# DB_Power-X01.net
KiCad netlist of a schematic drawn in Altium Designer
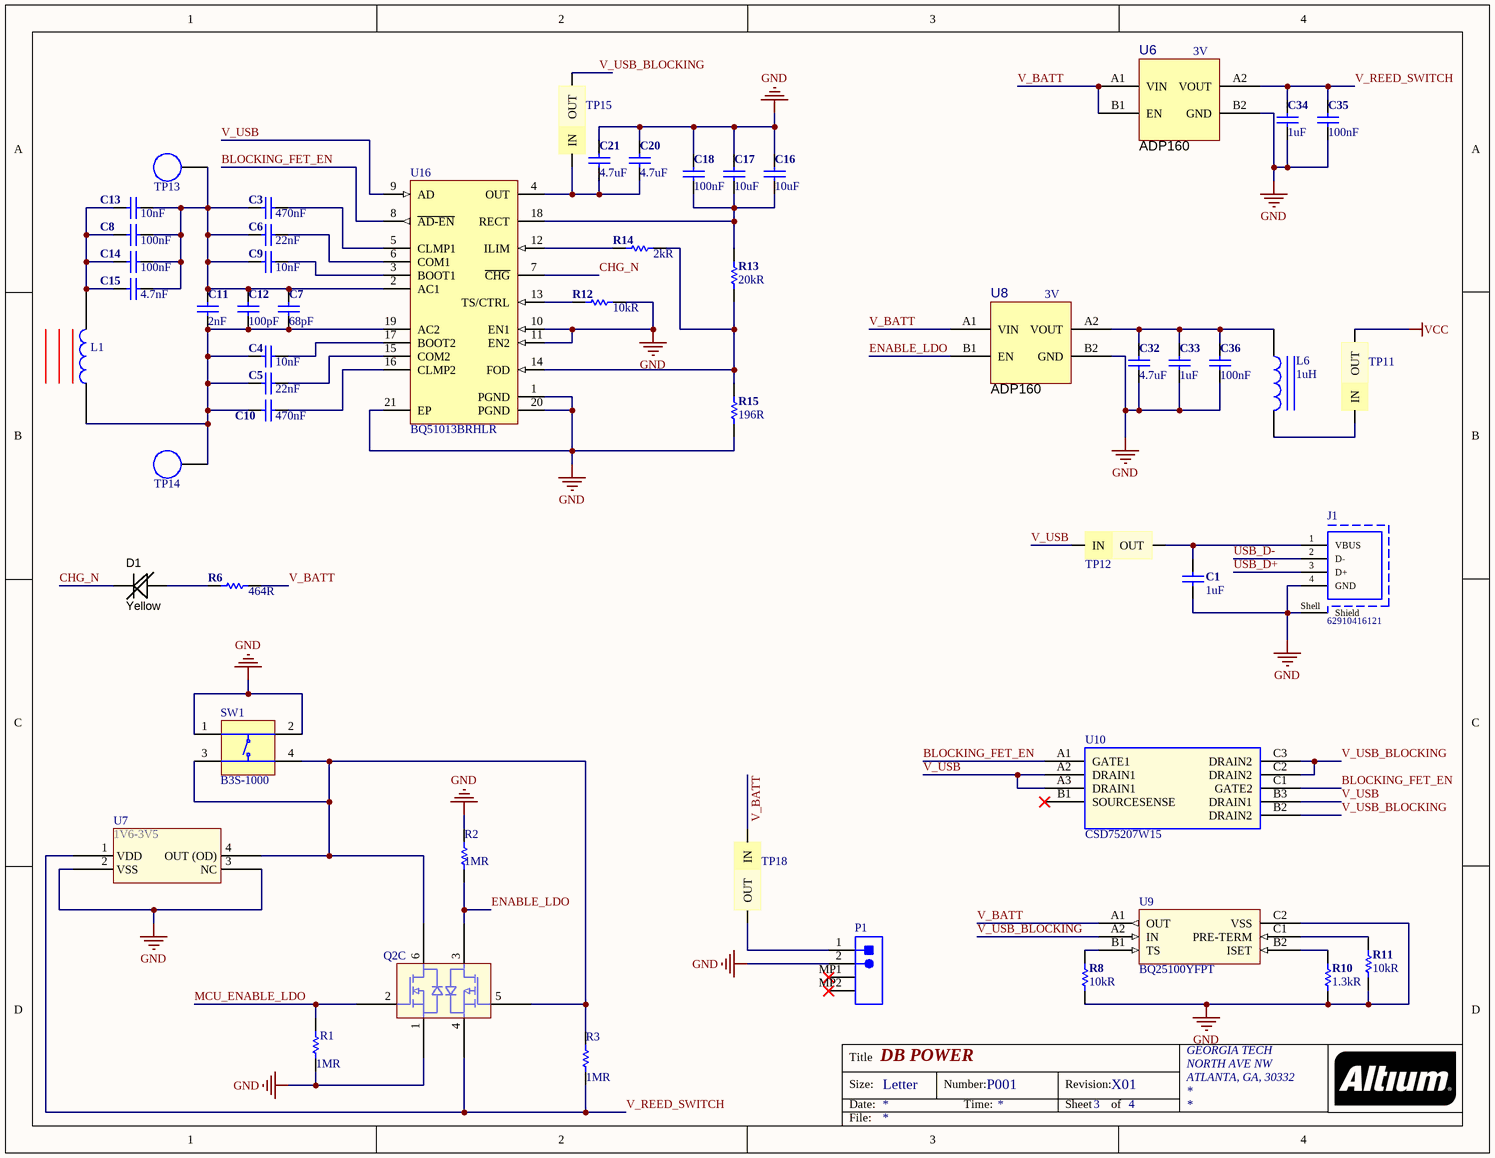
[diagram p0: DB_Power-X01.SchDoc]

(export (version "E")
  (design (tool "Eeschema 10.0.6"))
  (components
    (comp (ref "C1")
      (value "1uF")
      (footprint "C0402")
      (fields
        (field (name "MANUFACTURER") "Yageo")
        (field (name "MANUFACTURER PART NUMBER") "CC0402MRX5R5BB105")
        (field (name "TOLERANCE") "20%")
      )
      (libsource (lib "DB-X01") (part "C-0402(1005)"))
    )
    (comp (ref "C3")
      (value "470nF")
      (footprint "C0402")
      (fields
        (field (name "MANUFACTURER") "Murata")
        (field (name "MANUFACTURER PART NUMBER") "GRT155R61E474ME01D")
        (field (name "TOLERANCE") "20%")
      )
      (libsource (lib "DB-X01") (part "C-0402(1005)"))
    )
    (comp (ref "C4")
      (value "10nF")
      (footprint "C0402")
      (fields
        (field (name "MANUFACTURER") "KEMET")
        (field (name "MANUFACTURER PART NUMBER") "C0402C103J3RACTU")
        (field (name "TOLERANCE") "5%")
      )
      (libsource (lib "DB-X01") (part "C-0402(1005)"))
    )
    (comp (ref "C5")
      (value "22nF")
      (footprint "C0402")
      (fields
        (field (name "MANUFACTURER") "Murata")
        (field (name "MANUFACTURER PART NUMBER") "GRM155R71E223KA61D")
        (field (name "TOLERANCE") "10%")
      )
      (libsource (lib "DB-X01") (part "C-0402(1005)"))
    )
    (comp (ref "C6")
      (value "22nF")
      (footprint "C0402")
      (fields
        (field (name "MANUFACTURER") "Murata")
        (field (name "MANUFACTURER PART NUMBER") "GRM155R71E223KA61D")
        (field (name "TOLERANCE") "10%")
      )
      (libsource (lib "DB-X01") (part "C-0402(1005)"))
    )
    (comp (ref "C7")
      (value "68pF")
      (footprint "C0402")
      (fields
        (field (name "MANUFACTURER") "KEMET")
        (field (name "MANUFACTURER PART NUMBER") "CBR04C680F3GAC")
        (field (name "TOLERANCE") "1%")
      )
      (libsource (lib "DB-X01") (part "C-0402(1005)"))
    )
    (comp (ref "C8")
      (value "100nF")
      (footprint "C0402")
      (fields
        (field (name "MANUFACTURER") "Taiyo Yuden")
        (field (name "MANUFACTURER PART NUMBER") "TMK105BJ104KV-F")
        (field (name "TOLERANCE") "10%")
      )
      (libsource (lib "DB-X01") (part "C-0402(1005)"))
    )
    (comp (ref "C9")
      (value "10nF")
      (footprint "C0402")
      (fields
        (field (name "MANUFACTURER") "KEMET")
        (field (name "MANUFACTURER PART NUMBER") "C0402C103J3RACTU")
        (field (name "TOLERANCE") "5%")
      )
      (libsource (lib "DB-X01") (part "C-0402(1005)"))
    )
    (comp (ref "C10")
      (value "470nF")
      (footprint "C0402")
      (fields
        (field (name "MANUFACTURER") "Murata")
        (field (name "MANUFACTURER PART NUMBER") "GRT155R61E474ME01D")
        (field (name "TOLERANCE") "20%")
      )
      (libsource (lib "DB-X01") (part "C-0402(1005)"))
    )
    (comp (ref "C11")
      (value "2nF")
      (footprint "C0402")
      (fields
        (field (name "MANUFACTURER") "KEMET")
        (field (name "MANUFACTURER PART NUMBER") "C0402C202J3GACTU")
        (field (name "TOLERANCE") "5%")
      )
      (libsource (lib "DB-X01") (part "C-0402(1005)"))
    )
    (comp (ref "C12")
      (value "100pF")
      (footprint "C0402")
      (fields
        (field (name "MANUFACTURER") "KEMET")
        (field (name "MANUFACTURER PART NUMBER") "CBR04C101F3GAC")
        (field (name "TOLERANCE") "1%")
      )
      (libsource (lib "DB-X01") (part "C-0402(1005)"))
    )
    (comp (ref "C13")
      (value "10nF")
      (footprint "C0402")
      (fields
        (field (name "MANUFACTURER") "Yageo")
        (field (name "MANUFACTURER PART NUMBER") "CC0402JRX7R8BB103")
        (field (name "TOLERANCE") "5%")
      )
      (libsource (lib "DB-X01") (part "C-0402(1005)"))
    )
    (comp (ref "C14")
      (value "100nF")
      (footprint "C0402")
      (fields
        (field (name "MANUFACTURER") "Taiyo Yuden")
        (field (name "MANUFACTURER PART NUMBER") "TMK105BJ104KV-F")
        (field (name "TOLERANCE") "10%")
      )
      (libsource (lib "DB-X01") (part "C-0402(1005)"))
    )
    (comp (ref "C15")
      (value "4.7nF")
      (footprint "C0402")
      (fields
        (field (name "MANUFACTURER") "Yageo")
        (field (name "MANUFACTURER PART NUMBER") "CC0402JRX7R8BB472")
        (field (name "TOLERANCE") "5%")
      )
      (libsource (lib "DB-X01") (part "C-0402(1005)"))
    )
    (comp (ref "C16")
      (value "10uF")
      (footprint "C0603")
      (fields
        (field (name "MANUFACTURER") "Murata")
        (field (name "MANUFACTURER PART NUMBER") "GRM188R61E106MA73J")
        (field (name "TOLERANCE") "20%")
      )
      (libsource (lib "DB-X01") (part "C-0603(1608)"))
    )
    (comp (ref "C17")
      (value "10uF")
      (footprint "C0603")
      (fields
        (field (name "MANUFACTURER") "Murata")
        (field (name "MANUFACTURER PART NUMBER") "GRM188R61E106MA73J")
        (field (name "TOLERANCE") "20%")
      )
      (libsource (lib "DB-X01") (part "C-0603(1608)"))
    )
    (comp (ref "C18")
      (value "100nF")
      (footprint "C0603")
      (fields
        (field (name "MANUFACTURER") "Yageo")
        (field (name "MANUFACTURER PART NUMBER") "CC0402ZRY5V8BB104")
        (field (name "TOLERANCE") "80%")
      )
      (libsource (lib "DB-X01") (part "C-0603(1608)"))
    )
    (comp (ref "C20")
      (value "4.7uF")
      (footprint "C0402")
      (description "0402 10 V 4.7 uF ±20% Tolerance X5R Multilayer Ceramic Chip Capacitor")
      (fields
        (field (name "MANUFACTURER") "Murata")
        (field (name "MANUFACTURER PART NUMBER") "GRM155R61A475MEAAD")
      )
      (libsource (lib "DB-X01") (part "C-0402(1005)"))
    )
    (comp (ref "C21")
      (value "4.7uF")
      (footprint "C0402")
      (description "0402 10 V 4.7 uF ±20% Tolerance X5R Multilayer Ceramic Chip Capacitor")
      (fields
        (field (name "MANUFACTURER") "Murata")
        (field (name "MANUFACTURER PART NUMBER") "GRM155R61A475MEAAD")
      )
      (libsource (lib "DB-X01") (part "C-0402(1005)"))
    )
    (comp (ref "C32")
      (value "4.7uF")
      (footprint "C0402")
      (description "0402 10 V 4.7 uF ±20% Tolerance X5R Multilayer Ceramic Chip Capacitor")
      (fields
        (field (name "MANUFACTURER") "Murata")
        (field (name "MANUFACTURER PART NUMBER") "GRM155R61A475MEAAD")
      )
      (libsource (lib "DB-X01") (part "C-0402(1005)"))
    )
    (comp (ref "C33")
      (value "1uF")
      (footprint "C0402")
      (fields
        (field (name "MANUFACTURER") "Yageo")
        (field (name "MANUFACTURER PART NUMBER") "CC0402MRX5R5BB105")
        (field (name "TOLERANCE") "20%")
      )
      (libsource (lib "DB-X01") (part "C-0402(1005)"))
    )
    (comp (ref "C34")
      (value "1uF")
      (footprint "C0402")
      (fields
        (field (name "MANUFACTURER") "Yageo")
        (field (name "MANUFACTURER PART NUMBER") "CC0402MRX5R5BB105")
        (field (name "TOLERANCE") "20%")
      )
      (libsource (lib "DB-X01") (part "C-0402(1005)"))
    )
    (comp (ref "C35")
      (value "100nF")
      (footprint "C0402")
      (fields
        (field (name "MANUFACTURER") "Taiyo Yuden")
        (field (name "MANUFACTURER PART NUMBER") "TMK105BJ104KV-F")
        (field (name "TOLERANCE") "10%")
      )
      (libsource (lib "DB-X01") (part "C-0402(1005)"))
    )
    (comp (ref "C36")
      (value "100nF")
      (footprint "C0402")
      (fields
        (field (name "MANUFACTURER") "Taiyo Yuden")
        (field (name "MANUFACTURER PART NUMBER") "TMK105BJ104KV-F")
        (field (name "TOLERANCE") "10%")
      )
      (libsource (lib "DB-X01") (part "C-0402(1005)"))
    )
    (comp (ref "D1")
      (value "Yellow")
      (footprint "LED_0402")
      (description "Single Color LED, Super Bright Yellow, Water Clear, 0.8mm")
      (fields
        (field (name "MANUFACTURER") "Kingbright")
        (field (name "MANUFACTURER PART NUMBER") "APHHS1005SYCK")
      )
      (libsource (lib "DB-X01") (part "LED_0402(1005)"))
    )
    (comp (ref "J1")
      (value "62910416121")
      (footprint "62910416121")
      (description "USB 2.0 Type B Receptacle WR-COM, Horizontal, SMT, with Pads and Pegs")
      (fields (field (name "MANUFACTURER") "Wurth Electronics"))
      (libsource (lib "Altium Content Vault") (part "WE-USB-4-1SHLD"))
    )
    (comp (ref "L1")
      (value "WIRELESS CHARGING COIL, RECEIVER")
      (footprint "760308101219")
      (description "General Purpose Inductor, 11.8uH, 10%, 1 Element")
      (fields
        (field (name "MANUFACTURER") "Wurth Electronics")
        (field (name "MANUFACTURER PART NUMBER") "760308101219")
      )
      (libsource (lib "DB-X01") (part "WIRELESS_CHARGING_COIL"))
    )
    (comp (ref "L6")
      (value "1uH")
      (footprint "L0402")
      (description "General Purpose Inductor, 1uH, 20%, 1 Element, Ferrite-Core, SMD, 0402")
      (fields
        (field (name "MANUFACTURER") "TDK")
        (field (name "MANUFACTURER PART NUMBER") "MLZ1005M1R0WT000")
      )
      (libsource (lib "DB-X01") (part "Inductor Iron"))
    )
    (comp (ref "P1")
      (value "B2B-PH-SM4-TB(LF)(SN)")
      (footprint "JST-B2B-PH-SM4-TB-2_V")
      (description "Male Header, Pitch 2 mm, 1 x 2 Position, Height 6.6 mm, RoHS, Tape and Reel")
      (fields (field (name "MANUFACTURER") "JST"))
      (libsource (lib "Altium Content Vault") (part "CN-1P-2M-R2"))
    )
    (comp (ref "Q2")
      (value "dual fet SSMini6")
      (footprint "SSMini6-F3-B")
      (fields
        (field (name "MANUFACTURER") "Panasonic")
        (field (name "MANUFACTURER PART NUMBER") "FG6943010R")
      )
      (libsource (lib "DB-X01") (part "FG6943010R"))
    )
    (comp (ref "R1")
      (value "AC0402FR-071ML")
      (footprint "RESC1005X37X25LL05T10")
      (description "100 ohm resistor")
      (fields
        (field (name "MANUFACTURER") "Yageo")
        (field (name "RESISTANCE") "1MR")
        (field (name "TOLERANCE") "1%")
      )
      (libsource (lib "Altium Content Vault") (part "RES"))
    )
    (comp (ref "R2")
      (value "AC0402FR-071ML")
      (footprint "RESC1005X37X25LL05T10")
      (description "100 ohm resistor")
      (fields
        (field (name "MANUFACTURER") "Yageo")
        (field (name "RESISTANCE") "1MR")
        (field (name "TOLERANCE") "1%")
      )
      (libsource (lib "Altium Content Vault") (part "RES"))
    )
    (comp (ref "R3")
      (value "AC0402FR-071ML")
      (footprint "RESC1005X37X25LL05T10")
      (description "100 ohm resistor")
      (fields
        (field (name "MANUFACTURER") "Yageo")
        (field (name "RESISTANCE") "1MR")
        (field (name "TOLERANCE") "1%")
      )
      (libsource (lib "Altium Content Vault") (part "RES"))
    )
    (comp (ref "R6")
      (value "464R")
      (footprint "R0402")
      (fields
        (field (name "MANUFACTURER") "Yageo")
        (field (name "MANUFACTURER PART NUMBER") "RC0402FR-07464RL")
        (field (name "TOLERANCE") "1%")
      )
      (libsource (lib "DB-X01") (part "R-0402(1005)"))
    )
    (comp (ref "R8")
      (value "10kR")
      (footprint "R0402")
      (fields
        (field (name "MANUFACTURER") "Yageo")
        (field (name "MANUFACTURER PART NUMBER") "AC0402FR-0710KL")
        (field (name "TOLERANCE") "1%")
      )
      (libsource (lib "DB-X01") (part "R-0402(1005)"))
    )
    (comp (ref "R10")
      (value "1.3kR")
      (footprint "R0402")
      (fields
        (field (name "MANUFACTURER") "Yageo")
        (field (name "MANUFACTURER PART NUMBER") "RC0402FR-071K3L")
        (field (name "TOLERANCE") "1%")
      )
      (libsource (lib "DB-X01") (part "R-0402(1005)"))
    )
    (comp (ref "R11")
      (value "10kR")
      (footprint "R0402")
      (fields
        (field (name "MANUFACTURER") "Yageo")
        (field (name "MANUFACTURER PART NUMBER") "AC0402FR-0710KL")
        (field (name "TOLERANCE") "1%")
      )
      (libsource (lib "DB-X01") (part "R-0402(1005)"))
    )
    (comp (ref "R12")
      (value "10kR")
      (footprint "R0402")
      (fields
        (field (name "MANUFACTURER") "Yageo")
        (field (name "MANUFACTURER PART NUMBER") "AC0402FR-0710KL")
        (field (name "TOLERANCE") "1%")
      )
      (libsource (lib "DB-X01") (part "R-0402(1005)"))
    )
    (comp (ref "R13")
      (value "20kR")
      (footprint "R0402")
      (fields
        (field (name "MANUFACTURER") "Yageo")
        (field (name "MANUFACTURER PART NUMBER") "AC0402FR-0720KL")
        (field (name "TOLERANCE") "1%")
      )
      (libsource (lib "DB-X01") (part "R-0402(1005)"))
    )
    (comp (ref "R14")
      (value "2kR")
      (footprint "R0402")
      (fields
        (field (name "MANUFACTURER") "Yageo")
        (field (name "MANUFACTURER PART NUMBER") "AC0402FR-072KL")
        (field (name "TOLERANCE") "1%")
      )
      (libsource (lib "DB-X01") (part "R-0402(1005)"))
    )
    (comp (ref "R15")
      (value "196R")
      (footprint "R0402")
      (fields
        (field (name "MANUFACTURER") "Vishay")
        (field (name "MANUFACTURER PART NUMBER") "CRCW0402196RFKED")
        (field (name "TOLERANCE") "1%")
      )
      (libsource (lib "DB-X01") (part "R-0402(1005)"))
    )
    (comp (ref "SW1")
      (value "B3S-1000")
      (footprint "OMRON-B3S-1000-4_V")
      (description "Sealed Tactile Switch, SPST-NO, 3 to 24 V, -25 to 70 degC, 4-Pin SMD, RoHS, Bulk")
      (fields (field (name "MANUFACTURER") "Omron") (field (name "MANUFACTURER PART NUMBER") "B3S-1000P"))
      (libsource (lib "Altium Content Vault") (part "SW-SPST-4_A"))
    )
    (comp (ref "TP11")
      (value "JUMPER")
      (footprint "JUMPER")
      (description "SHUNT LP W/HANDLE 2 POS 30AU")
      (fields
        (field (name "MANUFACTURER") "TE Connectivity")
        (field (name "MANUFACTURER PART NUMBER") "8815452")
      )
      (libsource (lib "") (part "JUMPER_2"))
    )
    (comp (ref "TP12")
      (value "JUMPER")
      (footprint "JUMPER")
      (description "SHUNT LP W/HANDLE 2 POS 30AU")
      (fields
        (field (name "MANUFACTURER") "TE Connectivity")
        (field (name "MANUFACTURER PART NUMBER") "8815452")
      )
      (libsource (lib "") (part "JUMPER_1"))
    )
    (comp (ref "TP13")
      (value "S1751-46R")
      (footprint "S1751-46R")
      (description "PC TEST POINT TIN SMD")
      (fields (field (name "MANUFACTURER") "Harwin Inc."))
      (libsource (lib "DB-X01") (part "S1751-46R"))
    )
    (comp (ref "TP14")
      (value "S1751-46R")
      (footprint "S1751-46R")
      (description "PC TEST POINT TIN SMD")
      (fields (field (name "MANUFACTURER") "Harwin Inc."))
      (libsource (lib "DB-X01") (part "S1751-46R"))
    )
    (comp (ref "TP15")
      (value "JUMPER")
      (footprint "JUMPER")
      (description "SHUNT LP W/HANDLE 2 POS 30AU")
      (fields
        (field (name "MANUFACTURER") "TE Connectivity")
        (field (name "MANUFACTURER PART NUMBER") "8815452")
      )
      (libsource (lib "") (part "JUMPER_2"))
    )
    (comp (ref "TP18")
      (value "JUMPER")
      (footprint "JUMPER")
      (description "SHUNT LP W/HANDLE 2 POS 30AU")
      (fields
        (field (name "MANUFACTURER") "TE Connectivity")
        (field (name "MANUFACTURER PART NUMBER") "8815452")
      )
      (libsource (lib "DB-X01") (part "JUMPER"))
    )
    (comp (ref "U6")
      (value "ADP160")
      (footprint "ADP160")
      (description "Fixed Positive LDO Regulator, 3V, 0.1V Dropout, CMOS, PBGA4")
      (fields
        (field (name "MANUFACTURER") "Analog Devices")
        (field (name "MANUFACTURER PART NUMBER") "ADP172ACBZ-3.0-R7")
        (field (name "OUTPUT VOLTAGE") "3V")
      )
      (libsource (lib "DB-X01") (part "ADP160"))
    )
    (comp (ref "U7")
      (value "S-5712ANSL2-I4T1U")
      (footprint "SNT-4A")
      (description "MAGNETIC SWITCH UNIPOLAR SNT-4A")
      (fields (field (name "MANUFACTURER") "ABLIC U.S.A."))
      (libsource (lib "DB-X01") (part "S-5712ANSL2-I4T1U"))
    )
    (comp (ref "U8")
      (value "ADP160")
      (footprint "ADP160")
      (description "Fixed Positive LDO Regulator, 3V, 0.1V Dropout, CMOS, PBGA4")
      (fields
        (field (name "MANUFACTURER") "Analog Devices")
        (field (name "MANUFACTURER PART NUMBER") "ADP172ACBZ-3.0-R7")
        (field (name "OUTPUT VOLTAGE") "3V")
      )
      (libsource (lib "DB-X01") (part "ADP160"))
    )
    (comp (ref "U9")
      (value "BQ25100YFPT")
      (footprint "YZP0006")
      (description "Power Supply Support Circuit")
      (fields (field (name "MANUFACTURER") "Texas Instruments"))
      (libsource (lib "DB-X01") (part "BQ25100YFPT"))
    )
    (comp (ref "U10")
      (value "CSD75207W15")
      (footprint "YZF0009")
      (description "Small Signal Field-Effect Transistor, P-Channel, Metal-oxide Semiconductor FET")
      (fields (field (name "MANUFACTURER") "Texas Instruments"))
      (libsource (lib "DB-X01") (part "CSD75207W15"))
    )
    (comp (ref "U16")
      (value "BQ51013BRHLR")
      (footprint "BQ51013BRHLR")
      (fields (field (name "MANUFACTURER") "Texas Instruments"))
      (libsource (lib "DB-X01") (part "TI-BQ51013B-RHL20"))
    )
  )
  (nets
    (net (code "1") (name "/BLOCKING_FET_EN") (class "Default")
      (node (ref "U10") (pin "A1") (pinfunction "GATE1_A1") (pintype "passive"))
      (node (ref "U10") (pin "C1") (pinfunction "GATE2_C1") (pintype "passive"))
      (node (ref "U16") (pin "8") (pinfunction "~{AD-EN}_8") (pintype "output"))
    )
    (net (code "2") (name "/CHG_N") (class "Default")
      (node (ref "D1") (pin "K") (pinfunction "K_K") (pintype "passive"))
      (node (ref "U16") (pin "7") (pinfunction "~{CHG}_7") (pintype "open_collector"))
    )
    (net (code "3") (name "/ENABLE_LDO") (class "Default")
      (node (ref "Q2") (pin "3") (pinfunction "D_3") (pintype "passive"))
      (node (ref "R2") (pin "1") (pinfunction "1_1") (pintype "passive"))
      (node (ref "U8") (pin "B1") (pinfunction "EN_B1") (pintype "passive"))
    )
    (net (code "4") (name "/MCU_ENABLE_LDO") (class "Default")
      (node (ref "Q2") (pin "2") (pinfunction "G_2") (pintype "passive"))
      (node (ref "R1") (pin "1") (pinfunction "1_1") (pintype "passive"))
    )
    (net (code "5") (name "/USB_D+") (class "Default")
      (node (ref "J1") (pin "3") (pinfunction "D+_3") (pintype "passive"))
    )
    (net (code "6") (name "/USB_D-") (class "Default")
      (node (ref "J1") (pin "2") (pinfunction "D-_2") (pintype "passive"))
    )
    (net (code "7") (name "/V_BATT") (class "Default")
      (node (ref "R6") (pin "2") (pinfunction "2_2") (pintype "passive"))
      (node (ref "TP18") (pin "1") (pinfunction "IN_1") (pintype "passive"))
      (node (ref "U6") (pin "A1") (pinfunction "VIN_A1") (pintype "passive"))
      (node (ref "U6") (pin "B1") (pinfunction "EN_B1") (pintype "passive"))
      (node (ref "U8") (pin "A1") (pinfunction "VIN_A1") (pintype "passive"))
      (node (ref "U9") (pin "A1") (pinfunction "OUT_A1") (pintype "output"))
    )
    (net (code "8") (name "/V_REED_SWITCH") (class "Default")
      (node (ref "C34") (pin "1") (pinfunction "1_1") (pintype "passive"))
      (node (ref "C35") (pin "2") (pinfunction "2_2") (pintype "passive"))
      (node (ref "Q2") (pin "4") (pinfunction "S_4") (pintype "passive"))
      (node (ref "R3") (pin "1") (pinfunction "1_1") (pintype "passive"))
      (node (ref "U6") (pin "A2") (pinfunction "VOUT_A2") (pintype "passive"))
      (node (ref "U7") (pin "1") (pinfunction "VDD_1") (pintype "passive"))
    )
    (net (code "9") (name "/V_USB") (class "Default")
      (node (ref "TP12") (pin "1") (pinfunction "IN_1") (pintype "passive"))
      (node (ref "U10") (pin "A2") (pinfunction "DRAIN1_A2") (pintype "passive"))
      (node (ref "U10") (pin "A3") (pinfunction "DRAIN1_A3") (pintype "passive"))
      (node (ref "U10") (pin "B3") (pinfunction "DRAIN1_B3") (pintype "passive"))
      (node (ref "U16") (pin "9") (pinfunction "AD_9") (pintype "input"))
    )
    (net (code "10") (name "/V_USB_BLOCKING") (class "Default")
      (node (ref "TP15") (pin "2") (pinfunction "OUT_2") (pintype "passive"))
      (node (ref "U10") (pin "B2") (pinfunction "DRAIN2_B2") (pintype "passive"))
      (node (ref "U10") (pin "C2") (pinfunction "DRAIN2_C2") (pintype "passive"))
      (node (ref "U10") (pin "C3") (pinfunction "DRAIN2_C3") (pintype "passive"))
      (node (ref "U9") (pin "A2") (pinfunction "IN_A2") (pintype "input"))
    )
    (net (code "11") (name "GND") (class "Default")
      (node (ref "C1") (pin "2") (pinfunction "2_2") (pintype "passive"))
      (node (ref "C16") (pin "2") (pinfunction "2_2") (pintype "passive"))
      (node (ref "C17") (pin "2") (pinfunction "2_2") (pintype "passive"))
      (node (ref "C18") (pin "2") (pinfunction "2_2") (pintype "passive"))
      (node (ref "C20") (pin "1") (pinfunction "1_1") (pintype "passive"))
      (node (ref "C21") (pin "1") (pinfunction "1_1") (pintype "passive"))
      (node (ref "C32") (pin "2") (pinfunction "2_2") (pintype "passive"))
      (node (ref "C33") (pin "2") (pinfunction "2_2") (pintype "passive"))
      (node (ref "C34") (pin "2") (pinfunction "2_2") (pintype "passive"))
      (node (ref "C35") (pin "1") (pinfunction "1_1") (pintype "passive"))
      (node (ref "C36") (pin "1") (pinfunction "1_1") (pintype "passive"))
      (node (ref "J1") (pin "4") (pinfunction "GND_4") (pintype "passive"))
      (node (ref "J1") (pin "Shell") (pinfunction "Shield_Shell") (pintype "passive"))
      (node (ref "P1") (pin "2") (pinfunction "2_2") (pintype "passive"))
      (node (ref "Q2") (pin "1") (pinfunction "S_1") (pintype "passive"))
      (node (ref "R1") (pin "2") (pinfunction "2_2") (pintype "passive"))
      (node (ref "R10") (pin "2") (pinfunction "2_2") (pintype "passive"))
      (node (ref "R11") (pin "1") (pinfunction "1_1") (pintype "passive"))
      (node (ref "R12") (pin "2") (pinfunction "2_2") (pintype "passive"))
      (node (ref "R15") (pin "1") (pinfunction "1_1") (pintype "passive"))
      (node (ref "R2") (pin "2") (pinfunction "2_2") (pintype "passive"))
      (node (ref "R8") (pin "1") (pinfunction "1_1") (pintype "passive"))
      (node (ref "SW1") (pin "1") (pinfunction "1_1") (pintype "passive"))
      (node (ref "SW1") (pin "2") (pinfunction "2_2") (pintype "passive"))
      (node (ref "U16") (pin "1") (pinfunction "PGND_1") (pintype "power_in"))
      (node (ref "U16") (pin "10") (pinfunction "EN1_10") (pintype "input"))
      (node (ref "U16") (pin "11") (pinfunction "EN2_11") (pintype "input"))
      (node (ref "U16") (pin "20") (pinfunction "PGND_20") (pintype "power_in"))
      (node (ref "U16") (pin "21") (pinfunction "EP_21") (pintype "passive"))
      (node (ref "U6") (pin "B2") (pinfunction "GND_B2") (pintype "passive"))
      (node (ref "U7") (pin "2") (pinfunction "VSS_2") (pintype "passive"))
      (node (ref "U7") (pin "3") (pinfunction "NC_3") (pintype "passive"))
      (node (ref "U8") (pin "B2") (pinfunction "GND_B2") (pintype "passive"))
      (node (ref "U9") (pin "C2") (pinfunction "VSS_C2") (pintype "power_in"))
    )
    (net (code "12") (name "Net-(C13-Pad1)") (class "Default")
      (node (ref "C13") (pin "1") (pinfunction "1_1") (pintype "passive"))
      (node (ref "C14") (pin "1") (pinfunction "1_1") (pintype "passive"))
      (node (ref "C15") (pin "1") (pinfunction "1_1") (pintype "passive"))
      (node (ref "C8") (pin "1") (pinfunction "1_1") (pintype "passive"))
      (node (ref "L1") (pin "2") (pinfunction "2_2") (pintype "passive"))
    )
    (net (code "13") (name "Net-(D1-PadA)") (class "Default")
      (node (ref "D1") (pin "A") (pinfunction "A_A") (pintype "passive"))
      (node (ref "R6") (pin "1") (pinfunction "1_1") (pintype "passive"))
    )
    (net (code "14") (name "Net-(J1-VBUS)") (class "Default")
      (node (ref "C1") (pin "1") (pinfunction "1_1") (pintype "passive"))
      (node (ref "J1") (pin "1") (pinfunction "VBUS_1") (pintype "passive"))
      (node (ref "TP12") (pin "2") (pinfunction "OUT_2") (pintype "passive"))
    )
    (net (code "15") (name "Net-(TP11-IN)") (class "Default")
      (node (ref "L6") (pin "2") (pinfunction "2_2") (pintype "passive"))
      (node (ref "TP11") (pin "1") (pinfunction "IN_1") (pintype "passive"))
    )
    (net (code "16") (name "Net-(TP15-IN)") (class "Default")
      (node (ref "C20") (pin "2") (pinfunction "2_2") (pintype "passive"))
      (node (ref "C21") (pin "2") (pinfunction "2_2") (pintype "passive"))
      (node (ref "TP15") (pin "1") (pinfunction "IN_1") (pintype "passive"))
      (node (ref "U16") (pin "4") (pinfunction "OUT_4") (pintype "power_in"))
    )
    (net (code "17") (name "Net-(TP18-OUT)") (class "Default")
      (node (ref "P1") (pin "1") (pinfunction "1_1") (pintype "passive"))
      (node (ref "TP18") (pin "2") (pinfunction "OUT_2") (pintype "passive"))
    )
    (net (code "18") (name "Net-(U7-OUT_(OD))") (class "Default")
      (node (ref "Q2") (pin "5") (pinfunction "G_5") (pintype "passive"))
      (node (ref "Q2") (pin "6") (pinfunction "D_6") (pintype "passive"))
      (node (ref "R3") (pin "2") (pinfunction "2_2") (pintype "passive"))
      (node (ref "SW1") (pin "3") (pinfunction "3_3") (pintype "passive"))
      (node (ref "SW1") (pin "4") (pinfunction "4_4") (pintype "passive"))
      (node (ref "U7") (pin "4") (pinfunction "OUT_(OD)_4") (pintype "passive"))
    )
    (net (code "19") (name "Net-(U8-VOUT)") (class "Default")
      (node (ref "C32") (pin "1") (pinfunction "1_1") (pintype "passive"))
      (node (ref "C33") (pin "1") (pinfunction "1_1") (pintype "passive"))
      (node (ref "C36") (pin "2") (pinfunction "2_2") (pintype "passive"))
      (node (ref "L6") (pin "1") (pinfunction "1_1") (pintype "passive"))
      (node (ref "U8") (pin "A2") (pinfunction "VOUT_A2") (pintype "passive"))
    )
    (net (code "20") (name "Net-(U9-ISET)") (class "Default")
      (node (ref "R10") (pin "1") (pinfunction "1_1") (pintype "passive"))
      (node (ref "U9") (pin "B2") (pinfunction "ISET_B2") (pintype "input"))
    )
    (net (code "21") (name "Net-(U9-PRE-TERM)") (class "Default")
      (node (ref "R11") (pin "2") (pinfunction "2_2") (pintype "passive"))
      (node (ref "U9") (pin "C1") (pinfunction "PRE-TERM_C1") (pintype "input"))
    )
    (net (code "22") (name "Net-(U9-TS)") (class "Default")
      (node (ref "R8") (pin "2") (pinfunction "2_2") (pintype "passive"))
      (node (ref "U9") (pin "B1") (pinfunction "TS_B1") (pintype "input"))
    )
    (net (code "23") (name "Net-(U16-AC1)") (class "Default")
      (node (ref "C11") (pin "1") (pinfunction "1_1") (pintype "passive"))
      (node (ref "C12") (pin "1") (pinfunction "1_1") (pintype "passive"))
      (node (ref "C13") (pin "2") (pinfunction "2_2") (pintype "passive"))
      (node (ref "C14") (pin "2") (pinfunction "2_2") (pintype "passive"))
      (node (ref "C15") (pin "2") (pinfunction "2_2") (pintype "passive"))
      (node (ref "C3") (pin "1") (pinfunction "1_1") (pintype "passive"))
      (node (ref "C6") (pin "1") (pinfunction "1_1") (pintype "passive"))
      (node (ref "C7") (pin "1") (pinfunction "1_1") (pintype "passive"))
      (node (ref "C8") (pin "2") (pinfunction "2_2") (pintype "passive"))
      (node (ref "C9") (pin "1") (pinfunction "1_1") (pintype "passive"))
      (node (ref "TP13") (pin "1") (pinfunction "1_1") (pintype "passive"))
      (node (ref "U16") (pin "2") (pinfunction "AC1_2") (pintype "power_in"))
    )
    (net (code "24") (name "Net-(U16-AC2)") (class "Default")
      (node (ref "C10") (pin "1") (pinfunction "1_1") (pintype "passive"))
      (node (ref "C11") (pin "2") (pinfunction "2_2") (pintype "passive"))
      (node (ref "C12") (pin "2") (pinfunction "2_2") (pintype "passive"))
      (node (ref "C4") (pin "1") (pinfunction "1_1") (pintype "passive"))
      (node (ref "C5") (pin "1") (pinfunction "1_1") (pintype "passive"))
      (node (ref "C7") (pin "2") (pinfunction "2_2") (pintype "passive"))
      (node (ref "L1") (pin "1") (pinfunction "1_1") (pintype "passive"))
      (node (ref "TP14") (pin "1") (pinfunction "1_1") (pintype "passive"))
      (node (ref "U16") (pin "19") (pinfunction "AC2_19") (pintype "power_in"))
    )
    (net (code "25") (name "Net-(U16-BOOT1)") (class "Default")
      (node (ref "C9") (pin "2") (pinfunction "2_2") (pintype "passive"))
      (node (ref "U16") (pin "3") (pinfunction "BOOT1_3") (pintype "passive"))
    )
    (net (code "26") (name "Net-(U16-BOOT2)") (class "Default")
      (node (ref "C4") (pin "2") (pinfunction "2_2") (pintype "passive"))
      (node (ref "U16") (pin "17") (pinfunction "BOOT2_17") (pintype "passive"))
    )
    (net (code "27") (name "Net-(U16-CLMP1)") (class "Default")
      (node (ref "C3") (pin "2") (pinfunction "2_2") (pintype "passive"))
      (node (ref "U16") (pin "5") (pinfunction "CLMP1_5") (pintype "open_collector"))
    )
    (net (code "28") (name "Net-(U16-CLMP2)") (class "Default")
      (node (ref "C10") (pin "2") (pinfunction "2_2") (pintype "passive"))
      (node (ref "U16") (pin "16") (pinfunction "CLMP2_16") (pintype "open_collector"))
    )
    (net (code "29") (name "Net-(U16-COM1)") (class "Default")
      (node (ref "C6") (pin "2") (pinfunction "2_2") (pintype "passive"))
      (node (ref "U16") (pin "6") (pinfunction "COM1_6") (pintype "open_collector"))
    )
    (net (code "30") (name "Net-(U16-COM2)") (class "Default")
      (node (ref "C5") (pin "2") (pinfunction "2_2") (pintype "passive"))
      (node (ref "U16") (pin "15") (pinfunction "COM2_15") (pintype "open_collector"))
    )
    (net (code "31") (name "Net-(U16-FOD)") (class "Default")
      (node (ref "R13") (pin "2") (pinfunction "2_2") (pintype "passive"))
      (node (ref "R14") (pin "2") (pinfunction "2_2") (pintype "passive"))
      (node (ref "R15") (pin "2") (pinfunction "2_2") (pintype "passive"))
      (node (ref "U16") (pin "14") (pinfunction "FOD_14") (pintype "input"))
    )
    (net (code "32") (name "Net-(U16-ILIM)") (class "Default")
      (node (ref "R14") (pin "1") (pinfunction "1_1") (pintype "passive"))
      (node (ref "U16") (pin "12") (pinfunction "ILIM_12") (pintype "input"))
    )
    (net (code "33") (name "Net-(U16-RECT)") (class "Default")
      (node (ref "C16") (pin "1") (pinfunction "1_1") (pintype "passive"))
      (node (ref "C17") (pin "1") (pinfunction "1_1") (pintype "passive"))
      (node (ref "C18") (pin "1") (pinfunction "1_1") (pintype "passive"))
      (node (ref "R13") (pin "1") (pinfunction "1_1") (pintype "passive"))
      (node (ref "U16") (pin "18") (pinfunction "RECT_18") (pintype "passive"))
    )
    (net (code "34") (name "Net-(U16-TS{slash}CTRL)") (class "Default")
      (node (ref "R12") (pin "1") (pinfunction "1_1") (pintype "passive"))
      (node (ref "U16") (pin "13") (pinfunction "TS/CTRL_13") (pintype "input"))
    )
    (net (code "35") (name "VCC") (class "Default")
      (node (ref "TP11") (pin "2") (pinfunction "OUT_2") (pintype "passive"))
    )
    (net (code "36") (name "unconnected-(P1-PadMP1)") (class "Default")
      (node (ref "P1") (pin "MP1") (pinfunction "MP1_MP1") (pintype "passive+no_connect"))
    )
    (net (code "37") (name "unconnected-(P1-PadMP2)") (class "Default")
      (node (ref "P1") (pin "MP2") (pinfunction "MP2_MP2") (pintype "passive+no_connect"))
    )
    (net (code "38") (name "unconnected-(U10-SOURCESENSE-PadB1)") (class "Default")
      (node (ref "U10") (pin "B1") (pinfunction "SOURCESENSE_B1") (pintype "passive+no_connect"))
    )
  )
)
